# BUTTONS_LEDS.net
KiCad netlist of a schematic drawn in Altium Designer
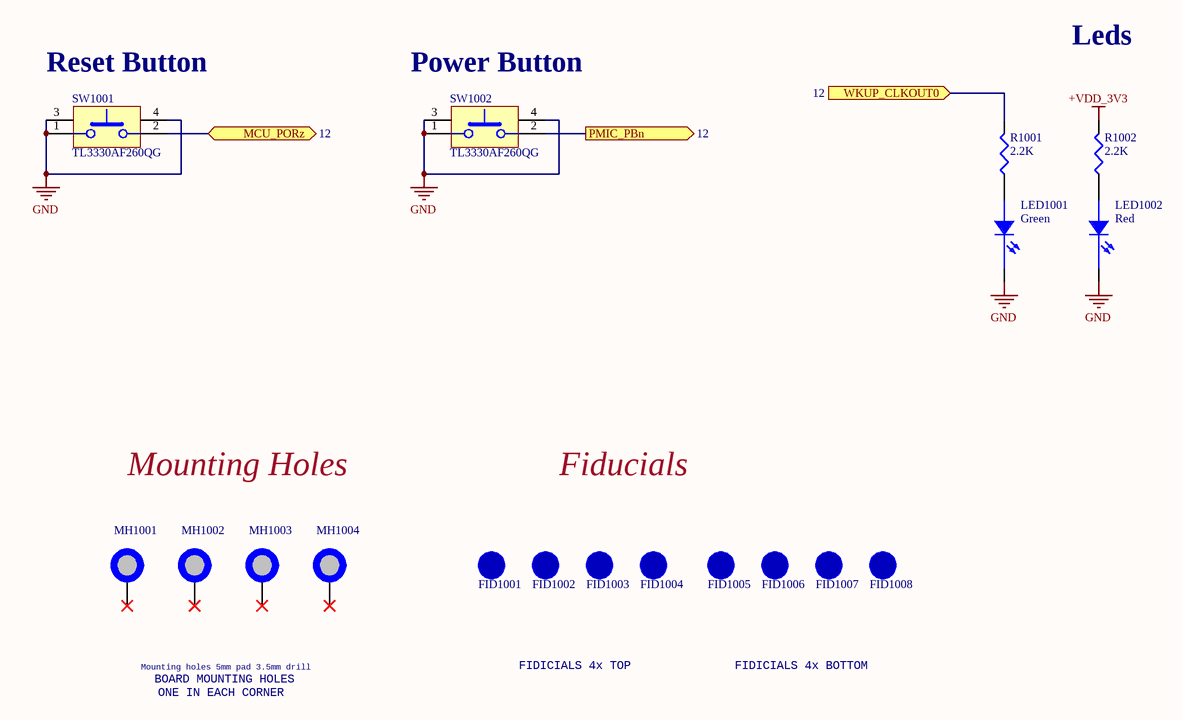
[diagram p0: BUTTONS&LEDS.SchDoc]

(export (version "E")
  (design (tool "Eeschema 10.0.6"))
  (components
    (comp (ref "FID1001")
      (value "FID_1MMC")
      (footprint "FID_40X120D")
      (description "Fiducial 40mil Diameter, 120mil Mask")
      (libsource (lib "Schlib SOM AM625") (part "FID_1MMC"))
    )
    (comp (ref "FID1002")
      (value "FID_1MMC")
      (footprint "FID_40X120D")
      (description "Fiducial 40mil Diameter, 120mil Mask")
      (libsource (lib "Schlib SOM AM625") (part "FID_1MMC"))
    )
    (comp (ref "FID1003")
      (value "FID_1MMC")
      (footprint "FID_40X120D")
      (description "Fiducial 40mil Diameter, 120mil Mask")
      (libsource (lib "Schlib SOM AM625") (part "FID_1MMC"))
    )
    (comp (ref "FID1004")
      (value "FID_1MMC")
      (footprint "FID_40X120D")
      (description "Fiducial 40mil Diameter, 120mil Mask")
      (libsource (lib "Schlib SOM AM625") (part "FID_1MMC"))
    )
    (comp (ref "FID1005")
      (value "FID_1MMC")
      (footprint "FID_40X120D")
      (description "Fiducial 40mil Diameter, 120mil Mask")
      (libsource (lib "Schlib SOM AM625") (part "FID_1MMC"))
    )
    (comp (ref "FID1006")
      (value "FID_1MMC")
      (footprint "FID_40X120D")
      (description "Fiducial 40mil Diameter, 120mil Mask")
      (libsource (lib "Schlib SOM AM625") (part "FID_1MMC"))
    )
    (comp (ref "FID1007")
      (value "FID_1MMC")
      (footprint "FID_40X120D")
      (description "Fiducial 40mil Diameter, 120mil Mask")
      (libsource (lib "Schlib SOM AM625") (part "FID_1MMC"))
    )
    (comp (ref "FID1008")
      (value "FID_1MMC")
      (footprint "FID_40X120D")
      (description "Fiducial 40mil Diameter, 120mil Mask")
      (libsource (lib "Schlib SOM AM625") (part "FID_1MMC"))
    )
    (comp (ref "LED1001")
      (value "Green")
      (footprint "led0402_G")
      (description "Yellow Green 0402 1X.5X4MM")
      (fields
        (field (name "MANUFACTURER") "American Bright")
        (field (name "MANUFACTURER PART NUMBER") "BL-HGE37A-AV-TRB")
      )
      (libsource (lib "Schlib SOM AM625") (part "BL-HGE37A-AV-TRB"))
    )
    (comp (ref "LED1002")
      (value "Red")
      (footprint "led0402_R")
      (description "LED Uni-Color Red 2-Pin Chip 0402(1006Metric) T/R")
      (fields (field (name "MANUFACTURER") "Rohm") (field (name "MANUFACTURER PART NUMBER") "SML-P12U2TT86R"))
      (libsource (lib "Schlib SOM AM625") (part "SML-P12U2TT86R"))
    )
    (comp (ref "MH1001")
      (value "MH_5MMD_3.5MMH")
      (footprint "MH_5MMD_3.5MMH")
      (description "Mounting Hole 5mm Diameter, 3.5mm Hole")
      (libsource (lib "Schlib SOM AM625") (part "MH_5MMD_3.5MMH"))
    )
    (comp (ref "MH1002")
      (value "MH_5MMD_3.5MMH")
      (footprint "MH_5MMD_3.5MMH")
      (description "Mounting Hole 5mm Diameter, 3.5mm Hole")
      (libsource (lib "Schlib SOM AM625") (part "MH_5MMD_3.5MMH"))
    )
    (comp (ref "MH1003")
      (value "MH_5MMD_3.5MMH")
      (footprint "MH_5MMD_3.5MMH")
      (description "Mounting Hole 5mm Diameter, 3.5mm Hole")
      (libsource (lib "Schlib SOM AM625") (part "MH_5MMD_3.5MMH"))
    )
    (comp (ref "MH1004")
      (value "MH_5MMD_3.5MMH")
      (footprint "MH_5MMD_3.5MMH")
      (description "Mounting Hole 5mm Diameter, 3.5mm Hole")
      (libsource (lib "Schlib SOM AM625") (part "MH_5MMD_3.5MMH"))
    )
    (comp (ref "R1001")
      (value "2.2K")
      (footprint "R0402")
      (description "SMD Chip Resistor, 2.2 kOhm, ± 1%, 63 mW, 0402 [1005 Metric], Thick Film, General Purpose")
      (fields
        (field (name "MANUFACTURER") "Yageo")
        (field (name "MANUFACTURER PART NUMBER") "RC0402FR-072K2L")
      )
      (libsource (lib "Schlib SOM AM625") (part "RC0402FR-072K2L"))
    )
    (comp (ref "R1002")
      (value "2.2K")
      (footprint "R0402")
      (description "SMD Chip Resistor, 2.2 kOhm, ± 1%, 63 mW, 0402 [1005 Metric], Thick Film, General Purpose")
      (fields
        (field (name "MANUFACTURER") "Yageo")
        (field (name "MANUFACTURER PART NUMBER") "RC0402FR-072K2L")
      )
      (libsource (lib "Schlib SOM AM625") (part "RC0402FR-072K2L"))
    )
    (comp (ref "SW1001")
      (value "TL3330AF260QG")
      (footprint "SW_TL3330_EWI")
      (description "Switch Tactile N.O. SPST Rectangular Button Gull Wing 0.05A 12VDC 2.55N SMD")
      (fields (field (name "MANUFACTURER") "E-Switch"))
      (libsource (lib "Schlib SOM AM625") (part "TL3330AF260QG"))
    )
    (comp (ref "SW1002")
      (value "TL3330AF260QG")
      (footprint "SW_TL3330_EWI")
      (description "Switch Tactile N.O. SPST Rectangular Button Gull Wing 0.05A 12VDC 2.55N SMD")
      (fields (field (name "MANUFACTURER") "E-Switch"))
      (libsource (lib "Schlib SOM AM625") (part "TL3330AF260QG"))
    )
  )
  (nets
    (net (code "1") (name "+VDD_3V3") (class "Default")
      (node (ref "R1002") (pin "2") (pinfunction "2_2") (pintype "passive"))
    )
    (net (code "2") (name "/MCU_PORz") (class "Default")
      (node (ref "SW1001") (pin "2") (pinfunction "2_2") (pintype "passive"))
    )
    (net (code "3") (name "/PMIC_PBn") (class "Default")
      (node (ref "SW1002") (pin "2") (pinfunction "2_2") (pintype "passive"))
    )
    (net (code "4") (name "/WKUP_CLKOUT0") (class "Default")
      (node (ref "R1001") (pin "2") (pinfunction "2_2") (pintype "passive"))
    )
    (net (code "5") (name "GND") (class "Default")
      (node (ref "LED1001") (pin "2") (pinfunction "C_2") (pintype "passive"))
      (node (ref "LED1002") (pin "2") (pinfunction "C_2") (pintype "passive"))
      (node (ref "SW1001") (pin "1") (pinfunction "1_1") (pintype "passive"))
      (node (ref "SW1001") (pin "3") (pinfunction "MECH1_3") (pintype "passive"))
      (node (ref "SW1001") (pin "4") (pinfunction "MECH2_4") (pintype "passive"))
      (node (ref "SW1002") (pin "1") (pinfunction "1_1") (pintype "passive"))
      (node (ref "SW1002") (pin "3") (pinfunction "MECH1_3") (pintype "passive"))
      (node (ref "SW1002") (pin "4") (pinfunction "MECH2_4") (pintype "passive"))
    )
    (net (code "6") (name "Net-(LED1001-A)") (class "Default")
      (node (ref "LED1001") (pin "1") (pinfunction "A_1") (pintype "passive"))
      (node (ref "R1001") (pin "1") (pinfunction "1_1") (pintype "passive"))
    )
    (net (code "7") (name "Net-(LED1002-A)") (class "Default")
      (node (ref "LED1002") (pin "1") (pinfunction "A_1") (pintype "passive"))
      (node (ref "R1002") (pin "1") (pinfunction "1_1") (pintype "passive"))
    )
    (net (code "8") (name "unconnected-(MH1001-Pad1)") (class "Default")
      (node (ref "MH1001") (pin "1") (pinfunction "1_1") (pintype "passive+no_connect"))
    )
    (net (code "9") (name "unconnected-(MH1002-Pad1)") (class "Default")
      (node (ref "MH1002") (pin "1") (pinfunction "1_1") (pintype "passive+no_connect"))
    )
    (net (code "10") (name "unconnected-(MH1003-Pad1)") (class "Default")
      (node (ref "MH1003") (pin "1") (pinfunction "1_1") (pintype "passive+no_connect"))
    )
    (net (code "11") (name "unconnected-(MH1004-Pad1)") (class "Default")
      (node (ref "MH1004") (pin "1") (pinfunction "1_1") (pintype "passive+no_connect"))
    )
  )
)
